# BMP180.net
KiCad netlist of a schematic drawn in Altium Designer
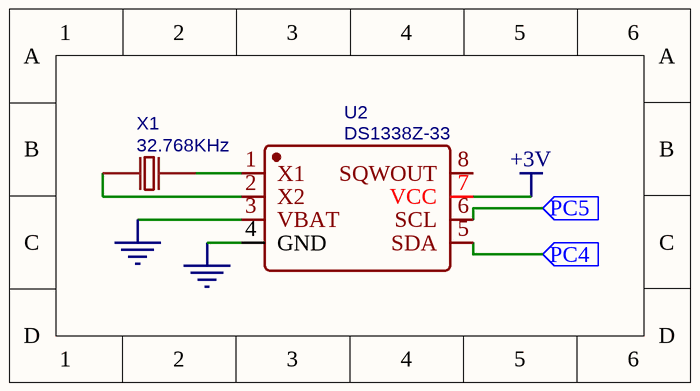
[diagram p0: BMP180.schdoc]

(export (version "E")
  (design (tool "Eeschema 10.0.6"))
  (components
    (comp (ref "U2")
      (value "DS1338Z-33")
      (fields (field (name "BOM_SUPPLIER PART") "C49105"))
      (libsource (lib "altium-import") (part "root_0_DS1338Z-33_"))
    )
    (comp (ref "X1")
      (value "32.768KHz")
      (fields
        (field (name "BOM_MANUFACTURER PART") "DT-38 32.768KHz")
        (field (name "BOM_SUPPLIER PART") "C93228")
      )
      (libsource (lib "altium-import") (part "root_2_32.768KHz_"))
    )
  )
  (nets
    (net (code "1") (name "+3V") (class "Default")
      (node (ref "U2") (pin "7") (pinfunction "VCC_7") (pintype "passive"))
    )
    (net (code "2") (name "/PC4") (class "Default")
      (node (ref "U2") (pin "5") (pinfunction "SDA_5") (pintype "passive"))
    )
    (net (code "3") (name "/PC5") (class "Default")
      (node (ref "U2") (pin "6") (pinfunction "SCL_6") (pintype "passive"))
    )
    (net (code "4") (name "GND") (class "Default")
      (node (ref "U2") (pin "3") (pinfunction "VBAT_3") (pintype "passive"))
      (node (ref "U2") (pin "4") (pinfunction "GND_4") (pintype "passive"))
    )
    (net (code "5") (name "Net-(U2-X1)") (class "Default")
      (node (ref "U2") (pin "1") (pinfunction "X1_1") (pintype "passive"))
      (node (ref "X1") (pin "2") (pinfunction "2_2") (pintype "passive"))
    )
    (net (code "6") (name "Net-(U2-X2)") (class "Default")
      (node (ref "U2") (pin "2") (pinfunction "X2_2") (pintype "passive"))
      (node (ref "X1") (pin "1") (pinfunction "1_1") (pintype "passive"))
    )
    (net (code "7") (name "unconnected-(U2-SQWOUT-Pad8)") (class "Default")
      (node (ref "U2") (pin "8") (pinfunction "SQWOUT_8") (pintype "passive"))
    )
  )
)
